# soilSensor.net
KiCad netlist of a schematic drawn in EAGLE
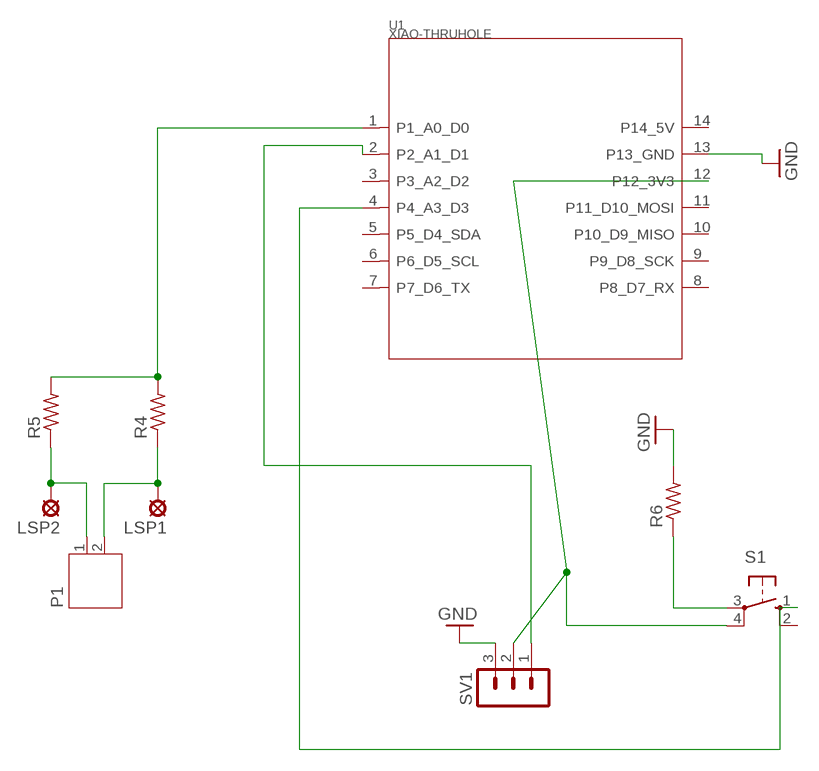
[diagram p0: schematic, sheet 1]

(export (version "E")
  (design (tool "Eeschema 10.0.6"))
  (components
    (comp (ref "LSP1")
      (value "LSP10")
      (footprint "eagle-import:LSP10")
      (libsource (lib "eagle-import") (part "LSP10"))
    )
    (comp (ref "LSP2")
      (value "LSP10")
      (footprint "eagle-import:LSP10")
      (libsource (lib "eagle-import") (part "LSP10"))
    )
    (comp (ref "P1")
      (value "JST-PH2")
      (footprint "eagle-import:JST-PH2")
      (libsource (lib "eagle-import") (part "JST-PH2"))
    )
    (comp (ref "R4")
      (value "R-US_0204/7")
      (footprint "eagle-import:0204_7")
      (libsource (lib "eagle-import") (part "R-US_0204/7"))
    )
    (comp (ref "R5")
      (value "R-US_0204/7")
      (footprint "eagle-import:0204_7")
      (libsource (lib "eagle-import") (part "R-US_0204/7"))
    )
    (comp (ref "R6")
      (value "R-US_0204/7")
      (footprint "eagle-import:0204_7")
      (libsource (lib "eagle-import") (part "R-US_0204/7"))
    )
    (comp (ref "S1")
      (value "10-XX")
      (footprint "eagle-import:B3F-10XX")
      (fields (field (name "MPN") "B3F-1000"))
      (libsource (lib "eagle-import") (part "10-XX"))
    )
    (comp (ref "SV1")
      (value "MA03-1")
      (footprint "eagle-import:MA03-1")
      (libsource (lib "eagle-import") (part "MA03-1"))
    )
    (comp (ref "U1")
      (value "XIAO-THRUHOLE")
      (footprint "eagle-import:XIAO-GENERIC-THRUHOLE-MODULE14P-2.54-21X17.8MM")
      (libsource (lib "eagle-import") (part "XIAO-THRUHOLE"))
    )
  )
  (nets
    (net (code "1") (name "GND") (class "Default")
      (node (ref "R6") (pin "2") (pinfunction "2_2") (pintype "passive"))
      (node (ref "SV1") (pin "3") (pinfunction "3_3") (pintype "passive"))
      (node (ref "U1") (pin "13") (pinfunction "P13_GND_13") (pintype "bidirectional"))
    )
    (net (code "2") (name "Net-(LSP1-PadMP)") (class "Default")
      (node (ref "LSP1") (pin "MP") (pinfunction "MP_MP") (pintype "passive"))
      (node (ref "P1") (pin "2") (pinfunction "2_2") (pintype "passive"))
      (node (ref "R4") (pin "1") (pinfunction "1_1") (pintype "passive"))
    )
    (net (code "3") (name "Net-(LSP2-PadMP)") (class "Default")
      (node (ref "LSP2") (pin "MP") (pinfunction "MP_MP") (pintype "passive"))
      (node (ref "P1") (pin "1") (pinfunction "1_1") (pintype "passive"))
      (node (ref "R5") (pin "1") (pinfunction "1_1") (pintype "passive"))
    )
    (net (code "4") (name "Net-(S1-P)") (class "Default")
      (node (ref "R6") (pin "1") (pinfunction "1_1") (pintype "passive"))
      (node (ref "S1") (pin "3") (pinfunction "P_3") (pintype "passive"))
    )
    (net (code "5") (name "Net-(S1-P1)") (class "Default")
      (node (ref "S1") (pin "4") (pinfunction "P1_4") (pintype "passive"))
      (node (ref "SV1") (pin "2") (pinfunction "2_2") (pintype "passive"))
      (node (ref "U1") (pin "12") (pinfunction "P12_3V3_12") (pintype "bidirectional"))
    )
    (net (code "6") (name "Net-(S1-S)") (class "Default")
      (node (ref "S1") (pin "1") (pinfunction "S_1") (pintype "passive"))
      (node (ref "U1") (pin "4") (pinfunction "P4_A3_D3_4") (pintype "bidirectional"))
    )
    (net (code "7") (name "Net-(U1-P1_A0_D0)") (class "Default")
      (node (ref "R4") (pin "2") (pinfunction "2_2") (pintype "passive"))
      (node (ref "R5") (pin "2") (pinfunction "2_2") (pintype "passive"))
      (node (ref "U1") (pin "1") (pinfunction "P1_A0_D0_1") (pintype "bidirectional"))
    )
    (net (code "8") (name "Net-(U1-P2_A1_D1)") (class "Default")
      (node (ref "SV1") (pin "1") (pinfunction "1_1") (pintype "passive"))
      (node (ref "U1") (pin "2") (pinfunction "P2_A1_D1_2") (pintype "bidirectional"))
    )
    (net (code "9") (name "unconnected-(S1-S1-Pad2)") (class "Default")
      (node (ref "S1") (pin "2") (pinfunction "S1_2") (pintype "passive"))
    )
    (net (code "10") (name "unconnected-(U1-P3_A2_D2-Pad3)") (class "Default")
      (node (ref "U1") (pin "3") (pinfunction "P3_A2_D2_3") (pintype "bidirectional"))
    )
    (net (code "11") (name "unconnected-(U1-P5_D4_SDA-Pad5)") (class "Default")
      (node (ref "U1") (pin "5") (pinfunction "P5_D4_SDA_5") (pintype "bidirectional"))
    )
    (net (code "12") (name "unconnected-(U1-P6_D5_SCL-Pad6)") (class "Default")
      (node (ref "U1") (pin "6") (pinfunction "P6_D5_SCL_6") (pintype "bidirectional"))
    )
    (net (code "13") (name "unconnected-(U1-P7_D6_TX-Pad7)") (class "Default")
      (node (ref "U1") (pin "7") (pinfunction "P7_D6_TX_7") (pintype "bidirectional"))
    )
    (net (code "14") (name "unconnected-(U1-P8_D7_RX-Pad8)") (class "Default")
      (node (ref "U1") (pin "8") (pinfunction "P8_D7_RX_8") (pintype "bidirectional"))
    )
    (net (code "15") (name "unconnected-(U1-P9_D8_SCK-Pad9)") (class "Default")
      (node (ref "U1") (pin "9") (pinfunction "P9_D8_SCK_9") (pintype "bidirectional"))
    )
    (net (code "16") (name "unconnected-(U1-P10_D9_MISO-Pad10)") (class "Default")
      (node (ref "U1") (pin "10") (pinfunction "P10_D9_MISO_10") (pintype "bidirectional"))
    )
    (net (code "17") (name "unconnected-(U1-P11_D10_MOSI-Pad11)") (class "Default")
      (node (ref "U1") (pin "11") (pinfunction "P11_D10_MOSI_11") (pintype "bidirectional"))
    )
    (net (code "18") (name "unconnected-(U1-P14_5V-Pad14)") (class "Default")
      (node (ref "U1") (pin "14") (pinfunction "P14_5V_14") (pintype "bidirectional"))
    )
  )
)
